# CAN-Breakout2021_neu_02.net
KiCad netlist of a schematic drawn in EAGLE
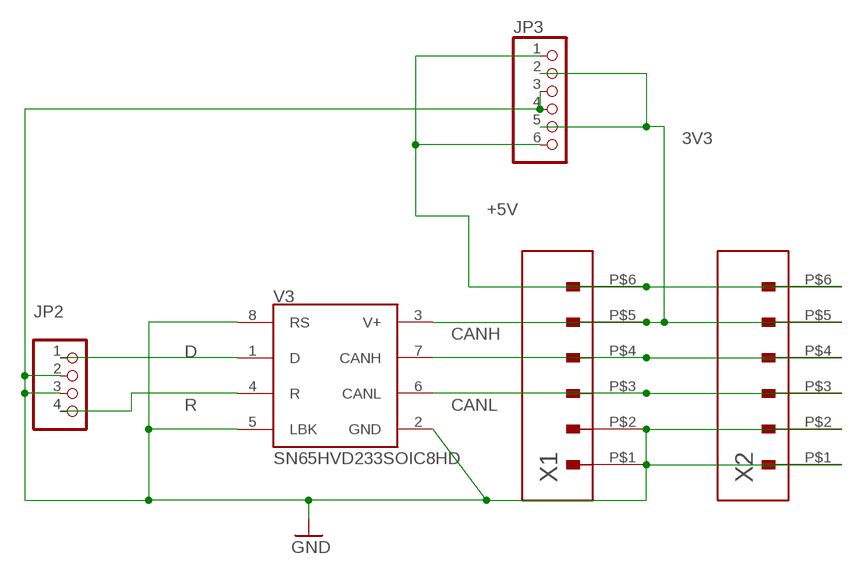
[diagram p0: schematic, sheet 1]

(export (version "E")
  (design (tool "Eeschema 10.0.6"))
  (components
    (comp (ref "JP2")
      (value "PINHD-1X4")
      (footprint "eagle-import:1X04")
      (libsource (lib "eagle-import") (part "PINHD-1X4"))
    )
    (comp (ref "JP3")
      (value "PINHD-1X6")
      (footprint "eagle-import:1X06")
      (libsource (lib "eagle-import") (part "PINHD-1X6"))
    )
    (comp (ref "V3")
      (value "SN65HVD233SOIC8HD")
      (footprint "eagle-import:SO08")
      (libsource (lib "eagle-import") (part "SN65HVD233HDSOIC8"))
    )
    (comp (ref "X1")
      (value "MOLEX104078-0610")
      (footprint "eagle-import:MOLEX104078-0610")
      (libsource (lib "eagle-import") (part "MOLEX104078-0610"))
    )
    (comp (ref "X2")
      (value "MOLEX104078-0610")
      (footprint "eagle-import:MOLEX104078-0610")
      (libsource (lib "eagle-import") (part "MOLEX104078-0610"))
    )
  )
  (nets
    (net (code "1") (name "/+5V") (class "Default")
      (node (ref "JP3") (pin "1") (pinfunction "1_1") (pintype "passive"))
      (node (ref "JP3") (pin "6") (pinfunction "6_6") (pintype "passive"))
      (node (ref "X1") (pin "P$6") (pinfunction "6_P$6") (pintype "passive"))
      (node (ref "X2") (pin "P$6") (pinfunction "6_P$6") (pintype "passive"))
    )
    (net (code "2") (name "/3V3") (class "Default")
      (node (ref "JP3") (pin "2") (pinfunction "2_2") (pintype "passive"))
      (node (ref "JP3") (pin "5") (pinfunction "5_5") (pintype "passive"))
      (node (ref "V3") (pin "3") (pinfunction "V+_3") (pintype "power_in"))
      (node (ref "X1") (pin "P$5") (pinfunction "5_P$5") (pintype "passive"))
      (node (ref "X2") (pin "P$5") (pinfunction "5_P$5") (pintype "passive"))
    )
    (net (code "3") (name "/CANH") (class "Default")
      (node (ref "V3") (pin "7") (pinfunction "CANH_7") (pintype "output"))
      (node (ref "X1") (pin "P$4") (pinfunction "4_P$4") (pintype "passive"))
      (node (ref "X2") (pin "P$4") (pinfunction "4_P$4") (pintype "passive"))
    )
    (net (code "4") (name "/CANL") (class "Default")
      (node (ref "V3") (pin "6") (pinfunction "CANL_6") (pintype "output"))
      (node (ref "X1") (pin "P$3") (pinfunction "3_P$3") (pintype "passive"))
      (node (ref "X2") (pin "P$3") (pinfunction "3_P$3") (pintype "passive"))
    )
    (net (code "5") (name "/D") (class "Default")
      (node (ref "JP2") (pin "1") (pinfunction "1_1") (pintype "passive"))
      (node (ref "V3") (pin "1") (pinfunction "D_1") (pintype "input"))
    )
    (net (code "6") (name "/R") (class "Default")
      (node (ref "JP2") (pin "4") (pinfunction "4_4") (pintype "passive"))
      (node (ref "V3") (pin "4") (pinfunction "R_4") (pintype "input"))
    )
    (net (code "7") (name "GND") (class "Default")
      (node (ref "JP2") (pin "2") (pinfunction "2_2") (pintype "passive"))
      (node (ref "JP2") (pin "3") (pinfunction "3_3") (pintype "passive"))
      (node (ref "JP3") (pin "3") (pinfunction "3_3") (pintype "passive"))
      (node (ref "JP3") (pin "4") (pinfunction "4_4") (pintype "passive"))
      (node (ref "V3") (pin "2") (pinfunction "GND_2") (pintype "power_in"))
      (node (ref "V3") (pin "5") (pinfunction "LBK_5") (pintype "input"))
      (node (ref "V3") (pin "8") (pinfunction "RS_8") (pintype "input"))
      (node (ref "X1") (pin "P$1") (pinfunction "1_P$1") (pintype "passive"))
      (node (ref "X1") (pin "P$2") (pinfunction "2_P$2") (pintype "passive"))
      (node (ref "X2") (pin "P$1") (pinfunction "1_P$1") (pintype "passive"))
      (node (ref "X2") (pin "P$2") (pinfunction "2_P$2") (pintype "passive"))
    )
  )
)
